# MICHA_nextPCB_servoA2.net
KiCad netlist of a schematic drawn in EAGLE
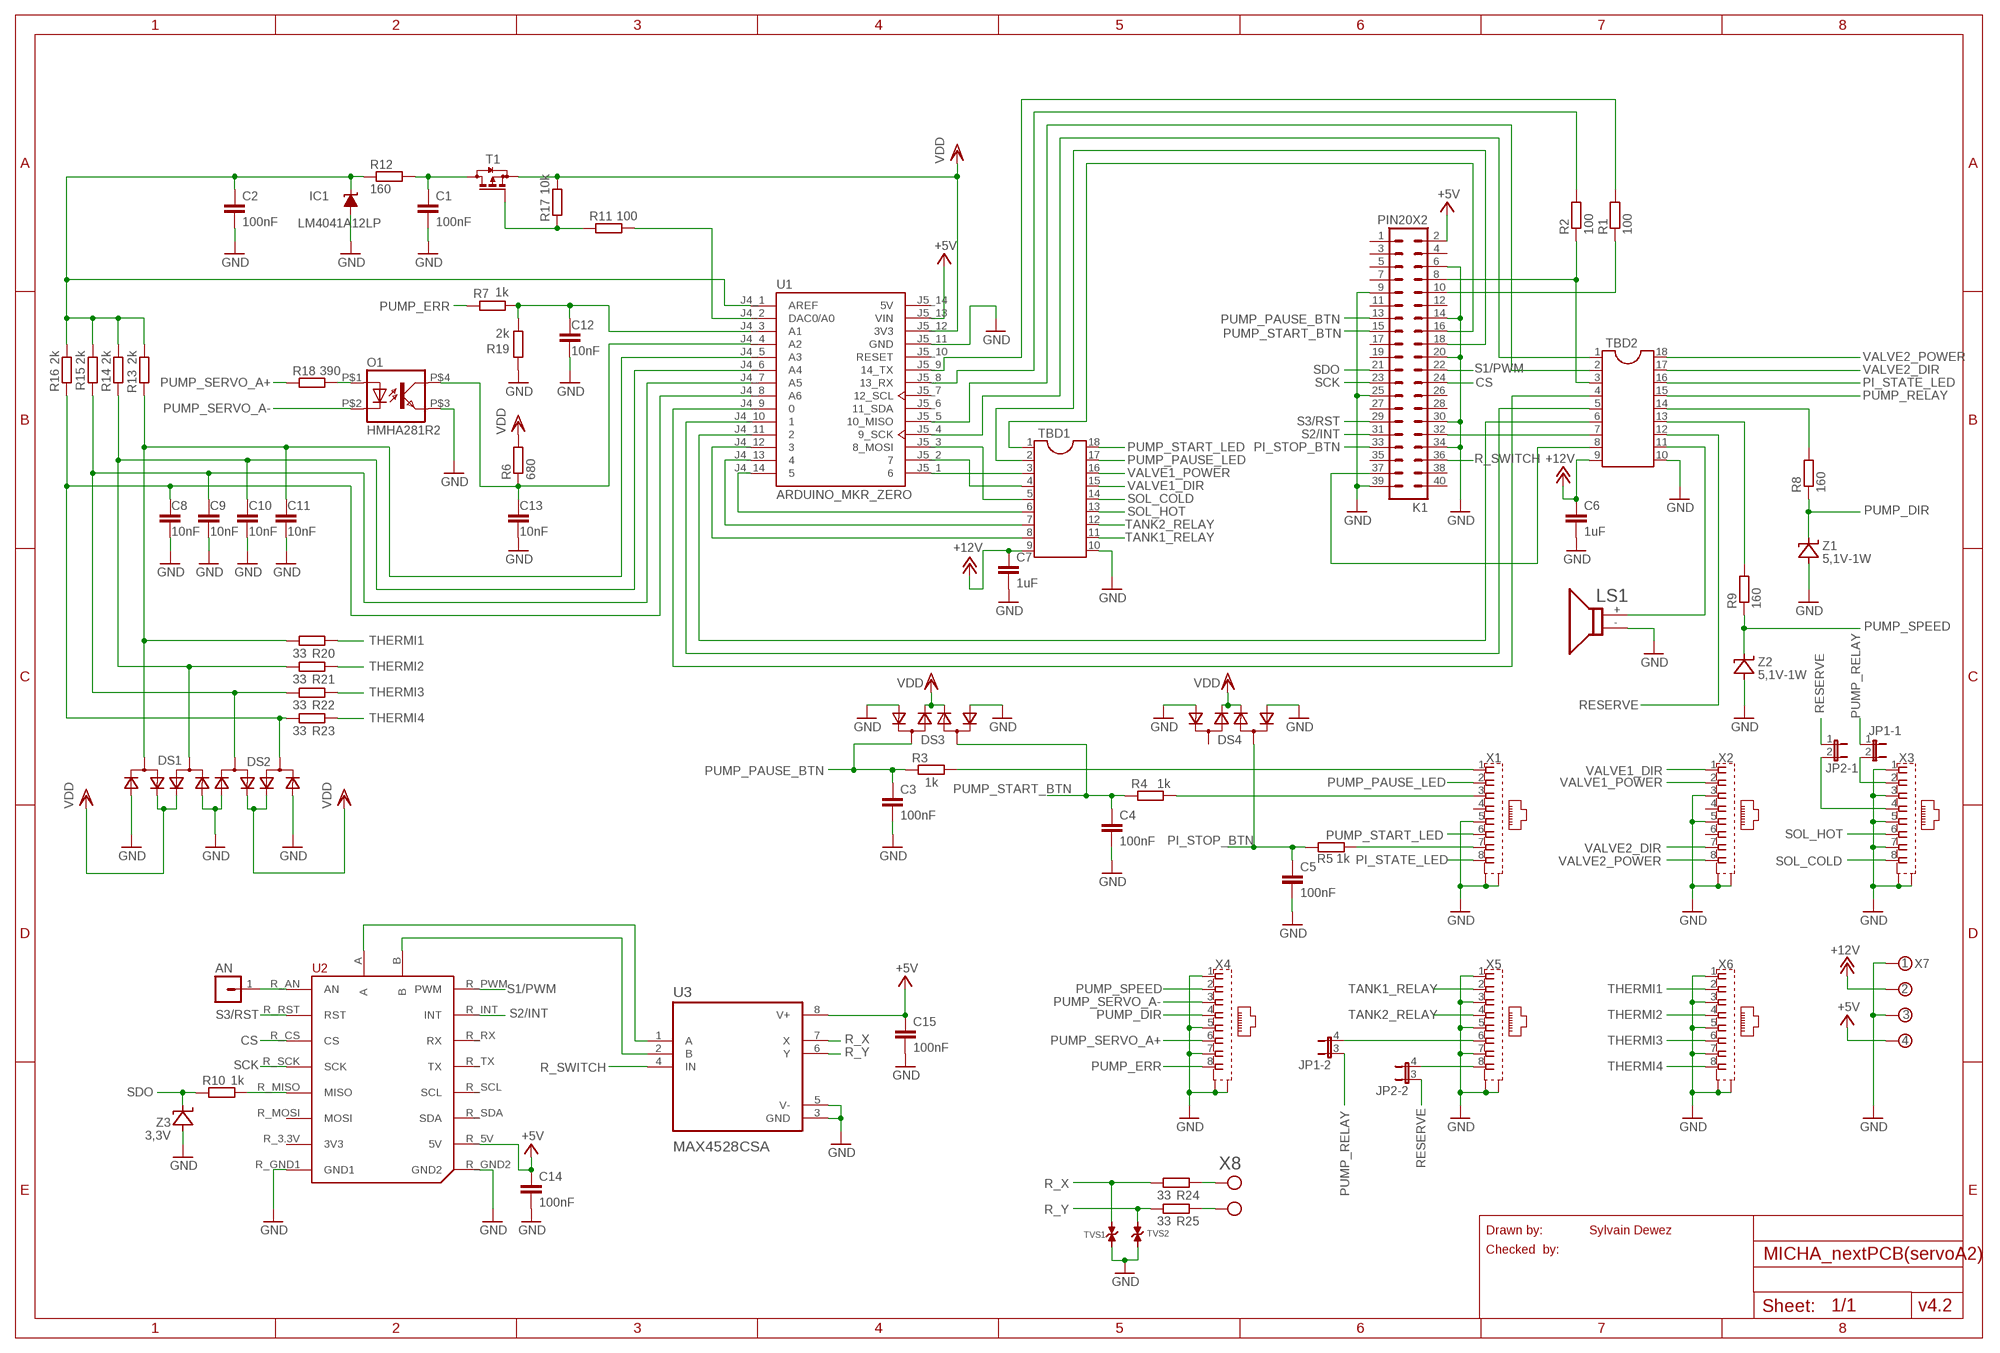
[diagram p0: schematic, sheet 1]

(export (version "E")
  (design (tool "Eeschema 10.0.6"))
  (components
    (comp (ref "AN")
      (value "MA01_PINHEADER")
      (footprint "eagle-import:MA01")
      (libsource (lib "eagle-import") (part "MA01_PINHEADER"))
    )
    (comp (ref "C1")
      (value "100nF")
      (footprint "eagle-import:C1206")
      (libsource (lib "eagle-import") (part "C-EUC1206"))
    )
    (comp (ref "C2")
      (value "100nF")
      (footprint "eagle-import:C1206")
      (libsource (lib "eagle-import") (part "C-EUC1206"))
    )
    (comp (ref "C3")
      (value "100nF")
      (footprint "eagle-import:C1206")
      (libsource (lib "eagle-import") (part "C-EUC1206"))
    )
    (comp (ref "C4")
      (value "100nF")
      (footprint "eagle-import:C1206")
      (libsource (lib "eagle-import") (part "C-EUC1206"))
    )
    (comp (ref "C5")
      (value "100nF")
      (footprint "eagle-import:C1206")
      (libsource (lib "eagle-import") (part "C-EUC1206"))
    )
    (comp (ref "C6")
      (value "1uF")
      (footprint "eagle-import:C1206")
      (libsource (lib "eagle-import") (part "C-EUC1206"))
    )
    (comp (ref "C7")
      (value "1uF")
      (footprint "eagle-import:C1206")
      (libsource (lib "eagle-import") (part "C-EUC1206"))
    )
    (comp (ref "C8")
      (value "10nF")
      (footprint "eagle-import:C1206")
      (libsource (lib "eagle-import") (part "C-EUC1206"))
    )
    (comp (ref "C9")
      (value "10nF")
      (footprint "eagle-import:C1206")
      (libsource (lib "eagle-import") (part "C-EUC1206"))
    )
    (comp (ref "C10")
      (value "10nF")
      (footprint "eagle-import:C1206")
      (libsource (lib "eagle-import") (part "C-EUC1206"))
    )
    (comp (ref "C11")
      (value "10nF")
      (footprint "eagle-import:C1206")
      (libsource (lib "eagle-import") (part "C-EUC1206"))
    )
    (comp (ref "C12")
      (value "10nF")
      (footprint "eagle-import:C1206")
      (libsource (lib "eagle-import") (part "C-EUC1206"))
    )
    (comp (ref "C13")
      (value "10nF")
      (footprint "eagle-import:C1206")
      (libsource (lib "eagle-import") (part "C-EUC1206"))
    )
    (comp (ref "C14")
      (value "100nF")
      (footprint "eagle-import:C1206")
      (libsource (lib "eagle-import") (part "C-EUC1206"))
    )
    (comp (ref "C15")
      (value "100nF")
      (footprint "eagle-import:C1206")
      (libsource (lib "eagle-import") (part "C-EUC1206"))
    )
    (comp (ref "DS1")
      (value "SDM10M45SD")
      (footprint "eagle-import:SDM10M45SD_SOT-26")
      (libsource (lib "eagle-import") (part "SDM10M45SD"))
    )
    (comp (ref "DS2")
      (value "SDM10M45SD")
      (footprint "eagle-import:SDM10M45SD_SOT-26")
      (libsource (lib "eagle-import") (part "SDM10M45SD"))
    )
    (comp (ref "DS3")
      (value "SDM10M45SD")
      (footprint "eagle-import:SDM10M45SD_SOT-26")
      (libsource (lib "eagle-import") (part "SDM10M45SD"))
    )
    (comp (ref "DS4")
      (value "SDM10M45SD")
      (footprint "eagle-import:SDM10M45SD_SOT-26")
      (libsource (lib "eagle-import") (part "SDM10M45SD"))
    )
    (comp (ref "IC1")
      (value "LM4041A12LP")
      (footprint "eagle-import:LP_O-PBCY-W3")
      (libsource (lib "eagle-import") (part "LM4041LPA12"))
    )
    (comp (ref "JP1")
      (value "JP2QE")
      (footprint "eagle-import:JP2Q")
      (libsource (lib "eagle-import") (part "JP2QE"))
    )
    (comp (ref "JP2")
      (value "JP2QE")
      (footprint "eagle-import:JP2Q")
      (libsource (lib "eagle-import") (part "JP2QE"))
    )
    (comp (ref "K1")
      (value "PIN20X2")
      (footprint "eagle-import:PIN_20X2")
      (libsource (lib "eagle-import") (part "PIN20X2"))
    )
    (comp (ref "LS1")
      (value "RSPRO-BUZZER-7800743")
      (footprint "eagle-import:RSPRO-BUZZER-7800743")
      (libsource (lib "eagle-import") (part "RSPRO-BUZZER-7800743"))
    )
    (comp (ref "O1")
      (value "HMHA281R2")
      (footprint "eagle-import:HMHA281R2")
      (libsource (lib "eagle-import") (part "HMHA281R2"))
    )
    (comp (ref "R1")
      (value "100")
      (footprint "eagle-import:R1206")
      (libsource (lib "eagle-import") (part "resistor_R-EU_R1206"))
    )
    (comp (ref "R2")
      (value "100")
      (footprint "eagle-import:R1206")
      (libsource (lib "eagle-import") (part "resistor_R-EU_R1206"))
    )
    (comp (ref "R3")
      (value "1k")
      (footprint "eagle-import:R1206")
      (libsource (lib "eagle-import") (part "resistor_R-EU_R1206"))
    )
    (comp (ref "R4")
      (value "1k")
      (footprint "eagle-import:R1206")
      (libsource (lib "eagle-import") (part "resistor_R-EU_R1206"))
    )
    (comp (ref "R5")
      (value "1k")
      (footprint "eagle-import:R1206")
      (libsource (lib "eagle-import") (part "resistor_R-EU_R1206"))
    )
    (comp (ref "R6")
      (value "680")
      (footprint "eagle-import:R1206")
      (libsource (lib "eagle-import") (part "resistor_R-EU_R1206"))
    )
    (comp (ref "R7")
      (value "1k")
      (footprint "eagle-import:R1206")
      (libsource (lib "eagle-import") (part "resistor_R-EU_R1206"))
    )
    (comp (ref "R8")
      (value "160")
      (footprint "eagle-import:R1206")
      (libsource (lib "eagle-import") (part "R-EU_R1206"))
    )
    (comp (ref "R9")
      (value "160")
      (footprint "eagle-import:R1206")
      (libsource (lib "eagle-import") (part "R-EU_R1206"))
    )
    (comp (ref "R10")
      (value "1k")
      (footprint "eagle-import:R1206")
      (libsource (lib "eagle-import") (part "resistor_R-EU_R1206"))
    )
    (comp (ref "R11")
      (value "100")
      (footprint "eagle-import:R1206")
      (libsource (lib "eagle-import") (part "resistor_R-EU_R1206"))
    )
    (comp (ref "R12")
      (value "160")
      (footprint "eagle-import:R1206")
      (libsource (lib "eagle-import") (part "R-EU_R1206"))
    )
    (comp (ref "R13")
      (value "2k")
      (footprint "eagle-import:R1206")
      (libsource (lib "eagle-import") (part "resistor_R-EU_R1206"))
    )
    (comp (ref "R14")
      (value "2k")
      (footprint "eagle-import:R1206")
      (libsource (lib "eagle-import") (part "resistor_R-EU_R1206"))
    )
    (comp (ref "R15")
      (value "2k")
      (footprint "eagle-import:R1206")
      (libsource (lib "eagle-import") (part "resistor_R-EU_R1206"))
    )
    (comp (ref "R16")
      (value "2k")
      (footprint "eagle-import:R1206")
      (libsource (lib "eagle-import") (part "resistor_R-EU_R1206"))
    )
    (comp (ref "R17")
      (value "10k")
      (footprint "eagle-import:R1206")
      (libsource (lib "eagle-import") (part "resistor_R-EU_R1206"))
    )
    (comp (ref "R18")
      (value "390")
      (footprint "eagle-import:R1206")
      (libsource (lib "eagle-import") (part "resistor_R-EU_R1206"))
    )
    (comp (ref "R19")
      (value "2k")
      (footprint "eagle-import:R1206")
      (libsource (lib "eagle-import") (part "resistor_R-EU_R1206"))
    )
    (comp (ref "R20")
      (value "33")
      (footprint "eagle-import:R1206")
      (libsource (lib "eagle-import") (part "resistor_R-EU_R1206"))
    )
    (comp (ref "R21")
      (value "33")
      (footprint "eagle-import:R1206")
      (libsource (lib "eagle-import") (part "resistor_R-EU_R1206"))
    )
    (comp (ref "R22")
      (value "33")
      (footprint "eagle-import:R1206")
      (libsource (lib "eagle-import") (part "resistor_R-EU_R1206"))
    )
    (comp (ref "R23")
      (value "33")
      (footprint "eagle-import:R1206")
      (libsource (lib "eagle-import") (part "resistor_R-EU_R1206"))
    )
    (comp (ref "R24")
      (value "33")
      (footprint "eagle-import:R1206")
      (libsource (lib "eagle-import") (part "resistor_R-EU_R1206"))
    )
    (comp (ref "R25")
      (value "33")
      (footprint "eagle-import:R1206")
      (libsource (lib "eagle-import") (part "resistor_R-EU_R1206"))
    )
    (comp (ref "T1")
      (value "BSS84")
      (footprint "eagle-import:SOT23")
      (libsource (lib "eagle-import") (part "BSS84"))
    )
    (comp (ref "TBD1")
      (value "DIL18S")
      (footprint "eagle-import:SOCKET-18")
      (libsource (lib "eagle-import") (part "DIL18S"))
    )
    (comp (ref "TBD2")
      (value "DIL18S")
      (footprint "eagle-import:SOCKET-18")
      (libsource (lib "eagle-import") (part "DIL18S"))
    )
    (comp (ref "TVS1")
      (value "TVS_SOD123")
      (footprint "eagle-import:TVS_SOD123")
      (libsource (lib "eagle-import") (part "TVS_SOD123"))
    )
    (comp (ref "TVS2")
      (value "TVS_SOD123")
      (footprint "eagle-import:TVS_SOD123")
      (libsource (lib "eagle-import") (part "TVS_SOD123"))
    )
    (comp (ref "U1")
      (value "ARDUINO_MKR_ZERO")
      (footprint "eagle-import:MODULE_ARDUINO_MKR_ZERO")
      (fields (field (name "MF") "Arduino") (field (name "MP") "ARDUINO MKR ZERO"))
      (libsource (lib "eagle-import") (part "ARDUINO_MKR_ZERO"))
    )
    (comp (ref "U2")
      (value "MIKROE_CLICK_UPGRADE")
      (footprint "eagle-import:MIKROE_BUS_MIDI_UPGRADE")
      (libsource (lib "eagle-import") (part "MIKROE_CLICK_UPGRADE"))
    )
    (comp (ref "U3")
      (value "MAX4528CSA")
      (footprint "eagle-import:SOIC127P600X175-8N")
      (fields (field (name "MF") "Maxim Integrated") (field (name "MP") "MAX4528CSA+"))
      (libsource (lib "eagle-import") (part "MAX4528CSA"))
    )
    (comp (ref "X1")
      (value "SS-7188S-A-NF_V2")
      (footprint "eagle-import:BEL_SS-7188S-A-NF")
      (fields (field (name "MF") "Stewart Connector") (field (name "MP") "SS-7188S-A-NF"))
      (libsource (lib "eagle-import") (part "SS-7188S-A-NF_V2"))
    )
    (comp (ref "X2")
      (value "SS-7188S-A-NF_V2")
      (footprint "eagle-import:BEL_SS-7188S-A-NF")
      (fields (field (name "MF") "Stewart Connector") (field (name "MP") "SS-7188S-A-NF"))
      (libsource (lib "eagle-import") (part "SS-7188S-A-NF_V2"))
    )
    (comp (ref "X3")
      (value "SS-7188S-A-NF_V2")
      (footprint "eagle-import:BEL_SS-7188S-A-NF")
      (fields (field (name "MF") "Stewart Connector") (field (name "MP") "SS-7188S-A-NF"))
      (libsource (lib "eagle-import") (part "SS-7188S-A-NF_V2"))
    )
    (comp (ref "X4")
      (value "SS-7188S-A-NF_V2")
      (footprint "eagle-import:BEL_SS-7188S-A-NF")
      (fields (field (name "MF") "Stewart Connector") (field (name "MP") "SS-7188S-A-NF"))
      (libsource (lib "eagle-import") (part "SS-7188S-A-NF_V2"))
    )
    (comp (ref "X5")
      (value "SS-7188S-A-NF_V2")
      (footprint "eagle-import:BEL_SS-7188S-A-NF")
      (fields (field (name "MF") "Stewart Connector") (field (name "MP") "SS-7188S-A-NF"))
      (libsource (lib "eagle-import") (part "SS-7188S-A-NF_V2"))
    )
    (comp (ref "X6")
      (value "SS-7188S-A-NF_V2")
      (footprint "eagle-import:BEL_SS-7188S-A-NF")
      (fields (field (name "MF") "Stewart Connector") (field (name "MP") "SS-7188S-A-NF"))
      (libsource (lib "eagle-import") (part "SS-7188S-A-NF_V2"))
    )
    (comp (ref "X7")
      (value "BUCHANAN_4_3.5MM")
      (footprint "eagle-import:BUCHANAN_4_3.5MM")
      (libsource (lib "eagle-import") (part "BUCHANAN_4_3.5MM"))
    )
    (comp (ref "X8")
      (value "MPT_0,5/_2-2,54_1725656_2")
      (footprint "eagle-import:PH_MPT_0,5__2-2,54_1725656")
      (fields (field (name "MF") "Phoenix Contact") (field (name "MP") "MPT 0,5/ 2-2,54 1725656"))
      (libsource (lib "eagle-import") (part "MPT_0,5/_2-2,54_1725656_2"))
    )
    (comp (ref "Z1")
      (value "5,1V-1W")
      (footprint "eagle-import:ZENER_SMA")
      (libsource (lib "eagle-import") (part "ZENER_SMA"))
    )
    (comp (ref "Z2")
      (value "5,1V-1W")
      (footprint "eagle-import:ZENER_SMA")
      (libsource (lib "eagle-import") (part "ZENER_SMA"))
    )
    (comp (ref "Z3")
      (value "3,3V")
      (footprint "eagle-import:ZENER_SMA")
      (libsource (lib "eagle-import") (part "ZENER_SMA"))
    )
  )
  (nets
    (net (code "1") (name "+5V") (class "Default")
      (node (ref "C14") (pin "1") (pinfunction "1_1") (pintype "passive"))
      (node (ref "C15") (pin "1") (pinfunction "1_1") (pintype "passive"))
      (node (ref "K1") (pin "2") (pinfunction "2_2") (pintype "passive"))
      (node (ref "U1") (pin "J5_13") (pinfunction "VIN_J5_13") (pintype "power_in"))
      (node (ref "U2") (pin "R_5V") (pinfunction "5V_R_5V") (pintype "bidirectional"))
      (node (ref "U3") (pin "8") (pinfunction "V+_8") (pintype "power_in"))
      (node (ref "X7") (pin "4") (pinfunction "KL3_4") (pintype "passive"))
    )
    (net (code "2") (name "+12V") (class "Default")
      (node (ref "C6") (pin "1") (pinfunction "1_1") (pintype "passive"))
      (node (ref "C7") (pin "1") (pinfunction "1_1") (pintype "passive"))
      (node (ref "TBD1") (pin "9") (pinfunction "9_9") (pintype "passive"))
      (node (ref "TBD2") (pin "9") (pinfunction "9_9") (pintype "passive"))
      (node (ref "X7") (pin "2") (pinfunction "KL1_2") (pintype "passive"))
    )
    (net (code "3") (name "/5V") (class "Default")
      (node (ref "U1") (pin "J5_14") (pinfunction "5V_J5_14") (pintype "power_in"))
    )
    (net (code "4") (name "/CS") (class "Default")
      (node (ref "K1") (pin "24") (pinfunction "24_24") (pintype "passive"))
      (node (ref "U2") (pin "R_CS") (pinfunction "CS_R_CS") (pintype "bidirectional"))
    )
    (net (code "5") (name "/PI_STATE_LED") (class "Default")
      (node (ref "TBD2") (pin "16") (pinfunction "16_16") (pintype "passive"))
      (node (ref "X1") (pin "8") (pinfunction "8_8") (pintype "passive"))
    )
    (net (code "6") (name "/PI_STOP_BTN") (class "Default")
      (node (ref "C5") (pin "1") (pinfunction "1_1") (pintype "passive"))
      (node (ref "DS4") (pin "3") (pinfunction "C1_3") (pintype "passive"))
      (node (ref "K1") (pin "33") (pinfunction "33_33") (pintype "passive"))
      (node (ref "R5") (pin "1") (pinfunction "1_1") (pintype "passive"))
    )
    (net (code "7") (name "/PUMP_DIR") (class "Default")
      (node (ref "R8") (pin "1") (pinfunction "1_1") (pintype "passive"))
      (node (ref "X4") (pin "4") (pinfunction "4_4") (pintype "passive"))
      (node (ref "Z1") (pin "C") (pinfunction "C_C") (pintype "passive"))
    )
    (net (code "8") (name "/PUMP_ERR") (class "Default")
      (node (ref "R7") (pin "1") (pinfunction "1_1") (pintype "passive"))
      (node (ref "X4") (pin "8") (pinfunction "8_8") (pintype "passive"))
    )
    (net (code "9") (name "/PUMP_PAUSE_BTN") (class "Default")
      (node (ref "C3") (pin "1") (pinfunction "1_1") (pintype "passive"))
      (node (ref "DS3") (pin "6") (pinfunction "C_6") (pintype "passive"))
      (node (ref "K1") (pin "13") (pinfunction "13_13") (pintype "passive"))
      (node (ref "R3") (pin "1") (pinfunction "1_1") (pintype "passive"))
    )
    (net (code "10") (name "/PUMP_PAUSE_LED") (class "Default")
      (node (ref "TBD1") (pin "17") (pinfunction "17_17") (pintype "passive"))
      (node (ref "X1") (pin "2") (pinfunction "2_2") (pintype "passive"))
    )
    (net (code "11") (name "/PUMP_RELAY") (class "Default")
      (node (ref "JP1") (pin "1") (pinfunction "1_1") (pintype "passive"))
      (node (ref "JP1") (pin "3") (pinfunction "1_3") (pintype "passive"))
      (node (ref "TBD2") (pin "15") (pinfunction "15_15") (pintype "passive"))
    )
    (net (code "12") (name "/PUMP_SERVO_A+") (class "Default")
      (node (ref "R18") (pin "1") (pinfunction "1_1") (pintype "passive"))
      (node (ref "X4") (pin "6") (pinfunction "6_6") (pintype "passive"))
    )
    (net (code "13") (name "/PUMP_SERVO_A-") (class "Default")
      (node (ref "O1") (pin "P$2") (pinfunction "C_P$2") (pintype "passive"))
      (node (ref "X4") (pin "3") (pinfunction "3_3") (pintype "passive"))
    )
    (net (code "14") (name "/PUMP_SPEED") (class "Default")
      (node (ref "R9") (pin "1") (pinfunction "1_1") (pintype "passive"))
      (node (ref "X4") (pin "2") (pinfunction "2_2") (pintype "passive"))
      (node (ref "Z2") (pin "C") (pinfunction "C_C") (pintype "passive"))
    )
    (net (code "15") (name "/PUMP_START_BTN") (class "Default")
      (node (ref "C4") (pin "1") (pinfunction "1_1") (pintype "passive"))
      (node (ref "DS3") (pin "3") (pinfunction "C1_3") (pintype "passive"))
      (node (ref "K1") (pin "15") (pinfunction "15_15") (pintype "passive"))
      (node (ref "R4") (pin "1") (pinfunction "1_1") (pintype "passive"))
    )
    (net (code "16") (name "/PUMP_START_LED") (class "Default")
      (node (ref "TBD1") (pin "18") (pinfunction "18_18") (pintype "passive"))
      (node (ref "X1") (pin "6") (pinfunction "6_6") (pintype "passive"))
    )
    (net (code "17") (name "/RESERVE") (class "Default")
      (node (ref "JP2") (pin "1") (pinfunction "1_1") (pintype "passive"))
      (node (ref "JP2") (pin "3") (pinfunction "1_3") (pintype "passive"))
      (node (ref "TBD2") (pin "12") (pinfunction "12_12") (pintype "passive"))
    )
    (net (code "18") (name "/R_SWITCH") (class "Default")
      (node (ref "K1") (pin "36") (pinfunction "36_36") (pintype "passive"))
      (node (ref "U3") (pin "4") (pinfunction "IN_4") (pintype "input"))
    )
    (net (code "19") (name "/R_X") (class "Default")
      (node (ref "R24") (pin "1") (pinfunction "1_1") (pintype "passive"))
      (node (ref "TVS1") (pin "P$1") (pinfunction "C_P$1") (pintype "passive"))
      (node (ref "U3") (pin "7") (pinfunction "X_7") (pintype "output"))
    )
    (net (code "20") (name "/R_Y") (class "Default")
      (node (ref "R25") (pin "1") (pinfunction "1_1") (pintype "passive"))
      (node (ref "TVS2") (pin "P$1") (pinfunction "C_P$1") (pintype "passive"))
      (node (ref "U3") (pin "6") (pinfunction "Y_6") (pintype "output"))
    )
    (net (code "21") (name "/S1{slash}PWM") (class "Default")
      (node (ref "K1") (pin "22") (pinfunction "22_22") (pintype "passive"))
      (node (ref "U2") (pin "R_PWM") (pinfunction "PWM_R_PWM") (pintype "bidirectional"))
    )
    (net (code "22") (name "/S2{slash}INT") (class "Default")
      (node (ref "K1") (pin "31") (pinfunction "31_31") (pintype "passive"))
      (node (ref "U2") (pin "R_INT") (pinfunction "INT_R_INT") (pintype "bidirectional"))
    )
    (net (code "23") (name "/S3{slash}RST") (class "Default")
      (node (ref "K1") (pin "29") (pinfunction "29_29") (pintype "passive"))
      (node (ref "U2") (pin "R_RST") (pinfunction "RST_R_RST") (pintype "bidirectional"))
    )
    (net (code "24") (name "/SCK") (class "Default")
      (node (ref "K1") (pin "23") (pinfunction "23_23") (pintype "passive"))
      (node (ref "U2") (pin "R_SCK") (pinfunction "SCK_R_SCK") (pintype "bidirectional"))
    )
    (net (code "25") (name "/SDO") (class "Default")
      (node (ref "K1") (pin "21") (pinfunction "21_21") (pintype "passive"))
      (node (ref "R10") (pin "1") (pinfunction "1_1") (pintype "passive"))
      (node (ref "Z3") (pin "C") (pinfunction "C_C") (pintype "passive"))
    )
    (net (code "26") (name "/SOL_COLD") (class "Default")
      (node (ref "TBD1") (pin "14") (pinfunction "14_14") (pintype "passive"))
      (node (ref "X3") (pin "8") (pinfunction "8_8") (pintype "passive"))
    )
    (net (code "27") (name "/SOL_HOT") (class "Default")
      (node (ref "TBD1") (pin "13") (pinfunction "13_13") (pintype "passive"))
      (node (ref "X3") (pin "6") (pinfunction "6_6") (pintype "passive"))
    )
    (net (code "28") (name "/TANK1_RELAY") (class "Default")
      (node (ref "TBD1") (pin "11") (pinfunction "11_11") (pintype "passive"))
      (node (ref "X5") (pin "2") (pinfunction "2_2") (pintype "passive"))
    )
    (net (code "29") (name "/TANK2_RELAY") (class "Default")
      (node (ref "TBD1") (pin "12") (pinfunction "12_12") (pintype "passive"))
      (node (ref "X5") (pin "4") (pinfunction "4_4") (pintype "passive"))
    )
    (net (code "30") (name "/THERMI1") (class "Default")
      (node (ref "R20") (pin "2") (pinfunction "2_2") (pintype "passive"))
      (node (ref "X6") (pin "2") (pinfunction "2_2") (pintype "passive"))
    )
    (net (code "31") (name "/THERMI2") (class "Default")
      (node (ref "R21") (pin "2") (pinfunction "2_2") (pintype "passive"))
      (node (ref "X6") (pin "4") (pinfunction "4_4") (pintype "passive"))
    )
    (net (code "32") (name "/THERMI3") (class "Default")
      (node (ref "R22") (pin "2") (pinfunction "2_2") (pintype "passive"))
      (node (ref "X6") (pin "6") (pinfunction "6_6") (pintype "passive"))
    )
    (net (code "33") (name "/THERMI4") (class "Default")
      (node (ref "R23") (pin "2") (pinfunction "2_2") (pintype "passive"))
      (node (ref "X6") (pin "8") (pinfunction "8_8") (pintype "passive"))
    )
    (net (code "34") (name "/VALVE1_DIR") (class "Default")
      (node (ref "TBD1") (pin "15") (pinfunction "15_15") (pintype "passive"))
      (node (ref "X2") (pin "1") (pinfunction "1_1") (pintype "passive"))
    )
    (net (code "35") (name "/VALVE1_POWER") (class "Default")
      (node (ref "TBD1") (pin "16") (pinfunction "16_16") (pintype "passive"))
      (node (ref "X2") (pin "2") (pinfunction "2_2") (pintype "passive"))
    )
    (net (code "36") (name "/VALVE2_DIR") (class "Default")
      (node (ref "TBD2") (pin "17") (pinfunction "17_17") (pintype "passive"))
      (node (ref "X2") (pin "7") (pinfunction "7_7") (pintype "passive"))
    )
    (net (code "37") (name "/VALVE2_POWER") (class "Default")
      (node (ref "TBD2") (pin "18") (pinfunction "18_18") (pintype "passive"))
      (node (ref "X2") (pin "8") (pinfunction "8_8") (pintype "passive"))
    )
    (net (code "38") (name "GND") (class "Default")
      (node (ref "C1") (pin "2") (pinfunction "2_2") (pintype "passive"))
      (node (ref "C10") (pin "2") (pinfunction "2_2") (pintype "passive"))
      (node (ref "C11") (pin "2") (pinfunction "2_2") (pintype "passive"))
      (node (ref "C12") (pin "2") (pinfunction "2_2") (pintype "passive"))
      (node (ref "C13") (pin "2") (pinfunction "2_2") (pintype "passive"))
      (node (ref "C14") (pin "2") (pinfunction "2_2") (pintype "passive"))
      (node (ref "C15") (pin "2") (pinfunction "2_2") (pintype "passive"))
      (node (ref "C2") (pin "2") (pinfunction "2_2") (pintype "passive"))
      (node (ref "C3") (pin "2") (pinfunction "2_2") (pintype "passive"))
      (node (ref "C4") (pin "2") (pinfunction "2_2") (pintype "passive"))
      (node (ref "C5") (pin "2") (pinfunction "2_2") (pintype "passive"))
      (node (ref "C6") (pin "2") (pinfunction "2_2") (pintype "passive"))
      (node (ref "C7") (pin "2") (pinfunction "2_2") (pintype "passive"))
      (node (ref "C8") (pin "2") (pinfunction "2_2") (pintype "passive"))
      (node (ref "C9") (pin "2") (pinfunction "2_2") (pintype "passive"))
      (node (ref "DS1") (pin "1") (pinfunction "A2_1") (pintype "passive"))
      (node (ref "DS1") (pin "4") (pinfunction "A3_4") (pintype "passive"))
      (node (ref "DS2") (pin "1") (pinfunction "A2_1") (pintype "passive"))
      (node (ref "DS2") (pin "4") (pinfunction "A3_4") (pintype "passive"))
      (node (ref "DS3") (pin "1") (pinfunction "A2_1") (pintype "passive"))
      (node (ref "DS3") (pin "4") (pinfunction "A3_4") (pintype "passive"))
      (node (ref "DS4") (pin "1") (pinfunction "A2_1") (pintype "passive"))
      (node (ref "DS4") (pin "4") (pinfunction "A3_4") (pintype "passive"))
      (node (ref "IC1") (pin "3") (pinfunction "A_3") (pintype "passive"))
      (node (ref "K1") (pin "14") (pinfunction "14_14") (pintype "passive"))
      (node (ref "K1") (pin "20") (pinfunction "20_20") (pintype "passive"))
      (node (ref "K1") (pin "25") (pinfunction "25_25") (pintype "passive"))
      (node (ref "K1") (pin "30") (pinfunction "30_30") (pintype "passive"))
      (node (ref "K1") (pin "34") (pinfunction "34_34") (pintype "passive"))
      (node (ref "K1") (pin "39") (pinfunction "39_39") (pintype "passive"))
      (node (ref "K1") (pin "6") (pinfunction "6_6") (pintype "passive"))
      (node (ref "K1") (pin "9") (pinfunction "9_9") (pintype "passive"))
      (node (ref "LS1") (pin "-") (pinfunction "2_-") (pintype "passive"))
      (node (ref "O1") (pin "P$3") (pinfunction "EMIT_P$3") (pintype "passive"))
      (node (ref "R19") (pin "1") (pinfunction "1_1") (pintype "passive"))
      (node (ref "TBD1") (pin "10") (pinfunction "10_10") (pintype "passive"))
      (node (ref "TBD2") (pin "10") (pinfunction "10_10") (pintype "passive"))
      (node (ref "TVS1") (pin "P$2") (pinfunction "C1_P$2") (pintype "passive"))
      (node (ref "TVS2") (pin "P$2") (pinfunction "C1_P$2") (pintype "passive"))
      (node (ref "U1") (pin "J5_11") (pinfunction "GND_J5_11") (pintype "power_in"))
      (node (ref "U2") (pin "R_GND1") (pinfunction "GND1_R_GND1") (pintype "bidirectional"))
      (node (ref "U2") (pin "R_GND2") (pinfunction "GND2_R_GND2") (pintype "bidirectional"))
      (node (ref "U3") (pin "3") (pinfunction "GND_3") (pintype "power_in"))
      (node (ref "U3") (pin "5") (pinfunction "V-_5") (pintype "power_in"))
      (node (ref "X1") (pin "5") (pinfunction "5_5") (pintype "passive"))
      (node (ref "X1") (pin "S1") (pinfunction "GND1_S1") (pintype "passive"))
      (node (ref "X1") (pin "S2") (pinfunction "GND2_S2") (pintype "passive"))
      (node (ref "X2") (pin "3") (pinfunction "3_3") (pintype "passive"))
      (node (ref "X2") (pin "5") (pinfunction "5_5") (pintype "passive"))
      (node (ref "X2") (pin "S1") (pinfunction "GND1_S1") (pintype "passive"))
      (node (ref "X2") (pin "S2") (pinfunction "GND2_S2") (pintype "passive"))
      (node (ref "X3") (pin "1") (pinfunction "1_1") (pintype "passive"))
      (node (ref "X3") (pin "3") (pinfunction "3_3") (pintype "passive"))
      (node (ref "X3") (pin "5") (pinfunction "5_5") (pintype "passive"))
      (node (ref "X3") (pin "7") (pinfunction "7_7") (pintype "passive"))
      (node (ref "X3") (pin "S1") (pinfunction "GND1_S1") (pintype "passive"))
      (node (ref "X3") (pin "S2") (pinfunction "GND2_S2") (pintype "passive"))
      (node (ref "X4") (pin "1") (pinfunction "1_1") (pintype "passive"))
      (node (ref "X4") (pin "5") (pinfunction "5_5") (pintype "passive"))
      (node (ref "X4") (pin "7") (pinfunction "7_7") (pintype "passive"))
      (node (ref "X4") (pin "S1") (pinfunction "GND1_S1") (pintype "passive"))
      (node (ref "X4") (pin "S2") (pinfunction "GND2_S2") (pintype "passive"))
      (node (ref "X5") (pin "1") (pinfunction "1_1") (pintype "passive"))
      (node (ref "X5") (pin "3") (pinfunction "3_3") (pintype "passive"))
      (node (ref "X5") (pin "5") (pinfunction "5_5") (pintype "passive"))
      (node (ref "X5") (pin "7") (pinfunction "7_7") (pintype "passive"))
      (node (ref "X5") (pin "S1") (pinfunction "GND1_S1") (pintype "passive"))
      (node (ref "X5") (pin "S2") (pinfunction "GND2_S2") (pintype "passive"))
      (node (ref "X6") (pin "1") (pinfunction "1_1") (pintype "passive"))
      (node (ref "X6") (pin "3") (pinfunction "3_3") (pintype "passive"))
      (node (ref "X6") (pin "5") (pinfunction "5_5") (pintype "passive"))
      (node (ref "X6") (pin "7") (pinfunction "7_7") (pintype "passive"))
      (node (ref "X6") (pin "S1") (pinfunction "GND1_S1") (pintype "passive"))
      (node (ref "X6") (pin "S2") (pinfunction "GND2_S2") (pintype "passive"))
      (node (ref "X7") (pin "1") (pinfunction "KL_1") (pintype "passive"))
      (node (ref "X7") (pin "3") (pinfunction "KL2_3") (pintype "passive"))
      (node (ref "Z1") (pin "A") (pinfunction "A_A") (pintype "passive"))
      (node (ref "Z2") (pin "A") (pinfunction "A_A") (pintype "passive"))
      (node (ref "Z3") (pin "A") (pinfunction "A_A") (pintype "passive"))
    )
    (net (code "39") (name "Net-(DS1-C)") (class "Default")
      (node (ref "C10") (pin "1") (pinfunction "1_1") (pintype "passive"))
      (node (ref "DS1") (pin "6") (pinfunction "C_6") (pintype "passive"))
      (node (ref "R14") (pin "2") (pinfunction "2_2") (pintype "passive"))
      (node (ref "R21") (pin "1") (pinfunction "1_1") (pintype "passive"))
      (node (ref "U1") (pin "J4_6") (pinfunction "A4_J4_6") (pintype "bidirectional"))
    )
    (net (code "40") (name "Net-(DS1-C1)") (class "Default")
      (node (ref "C11") (pin "1") (pinfunction "1_1") (pintype "passive"))
      (node (ref "DS1") (pin "3") (pinfunction "C1_3") (pintype "passive"))
      (node (ref "R13") (pin "2") (pinfunction "2_2") (pintype "passive"))
      (node (ref "R20") (pin "1") (pinfunction "1_1") (pintype "passive"))
      (node (ref "U1") (pin "J4_5") (pinfunction "A3_J4_5") (pintype "bidirectional"))
    )
    (net (code "41") (name "Net-(DS2-C)") (class "Default")
      (node (ref "C8") (pin "1") (pinfunction "1_1") (pintype "passive"))
      (node (ref "DS2") (pin "6") (pinfunction "C_6") (pintype "passive"))
      (node (ref "R16") (pin "2") (pinfunction "2_2") (pintype "passive"))
      (node (ref "R23") (pin "1") (pinfunction "1_1") (pintype "passive"))
      (node (ref "U1") (pin "J4_8") (pinfunction "A6_J4_8") (pintype "bidirectional"))
    )
    (net (code "42") (name "Net-(DS2-C1)") (class "Default")
      (node (ref "C9") (pin "1") (pinfunction "1_1") (pintype "passive"))
      (node (ref "DS2") (pin "3") (pinfunction "C1_3") (pintype "passive"))
      (node (ref "R15") (pin "2") (pinfunction "2_2") (pintype "passive"))
      (node (ref "R22") (pin "1") (pinfunction "1_1") (pintype "passive"))
      (node (ref "U1") (pin "J4_7") (pinfunction "A5_J4_7") (pintype "bidirectional"))
    )
    (net (code "43") (name "Net-(IC1-C)") (class "Default")
      (node (ref "C2") (pin "1") (pinfunction "1_1") (pintype "passive"))
      (node (ref "IC1") (pin "2") (pinfunction "C_2") (pintype "passive"))
      (node (ref "R12") (pin "1") (pinfunction "1_1") (pintype "passive"))
      (node (ref "R13") (pin "1") (pinfunction "1_1") (pintype "passive"))
      (node (ref "R14") (pin "1") (pinfunction "1_1") (pintype "passive"))
      (node (ref "R15") (pin "1") (pinfunction "1_1") (pintype "passive"))
      (node (ref "R16") (pin "1") (pinfunction "1_1") (pintype "passive"))
      (node (ref "U1") (pin "J4_1") (pinfunction "AREF_J4_1") (pintype "bidirectional"))
    )
    (net (code "44") (name "Net-(JP1-Pad2)") (class "Default")
      (node (ref "JP1") (pin "2") (pinfunction "2_2") (pintype "passive"))
      (node (ref "X3") (pin "2") (pinfunction "2_2") (pintype "passive"))
    )
    (net (code "45") (name "Net-(JP1B-2)") (class "Default")
      (node (ref "JP1") (pin "4") (pinfunction "2_4") (pintype "passive"))
      (node (ref "X5") (pin "6") (pinfunction "6_6") (pintype "passive"))
    )
    (net (code "46") (name "Net-(JP2-Pad2)") (class "Default")
      (node (ref "JP2") (pin "2") (pinfunction "2_2") (pintype "passive"))
      (node (ref "X3") (pin "4") (pinfunction "4_4") (pintype "passive"))
    )
    (net (code "47") (name "Net-(JP2B-2)") (class "Default")
      (node (ref "JP2") (pin "4") (pinfunction "2_4") (pintype "passive"))
      (node (ref "X5") (pin "8") (pinfunction "8_8") (pintype "passive"))
    )
    (net (code "48") (name "Net-(K1-Pad8)") (class "Default")
      (node (ref "K1") (pin "8") (pinfunction "8_8") (pintype "passive"))
      (node (ref "R2") (pin "1") (pinfunction "1_1") (pintype "passive"))
      (node (ref "TBD2") (pin "3") (pinfunction "3_3") (pintype "passive"))
    )
    (net (code "49") (name "Net-(K1-Pad10)") (class "Default")
      (node (ref "K1") (pin "10") (pinfunction "10_10") (pintype "passive"))
      (node (ref "R1") (pin "1") (pinfunction "1_1") (pintype "passive"))
    )
    (net (code "50") (name "Net-(K1-Pad16)") (class "Default")
      (node (ref "K1") (pin "16") (pinfunction "16_16") (pintype "passive"))
      (node (ref "TBD1") (pin "1") (pinfunction "1_1") (pintype "passive"))
    )
    (net (code "51") (name "Net-(K1-Pad18)") (class "Default")
      (node (ref "K1") (pin "18") (pinfunction "18_18") (pintype "passive"))
      (node (ref "TBD1") (pin "2") (pinfunction "2_2") (pintype "passive"))
    )
    (net (code "52") (name "Net-(K1-Pad32)") (class "Default")
      (node (ref "K1") (pin "32") (pinfunction "32_32") (pintype "passive"))
      (node (ref "TBD2") (pin "7") (pinfunction "7_7") (pintype "passive"))
    )
    (net (code "53") (name "Net-(K1-Pad37)") (class "Default")
      (node (ref "K1") (pin "37") (pinfunction "37_37") (pintype "passive"))
      (node (ref "TBD2") (pin "8") (pinfunction "8_8") (pintype "passive"))
    )
    (net (code "54") (name "Net-(LS1-1)") (class "Default")
      (node (ref "LS1") (pin "+") (pinfunction "1_+") (pintype "passive"))
      (node (ref "TBD2") (pin "11") (pinfunction "11_11") (pintype "passive"))
    )
    (net (code "55") (name "Net-(O1-A)") (class "Default")
      (node (ref "O1") (pin "P$1") (pinfunction "A_P$1") (pintype "passive"))
      (node (ref "R18") (pin "2") (pinfunction "2_2") (pintype "passive"))
    )
    (net (code "56") (name "Net-(O1-COL)") (class "Default")
      (node (ref "C13") (pin "1") (pinfunction "1_1") (pintype "passive"))
      (node (ref "O1") (pin "P$4") (pinfunction "COL_P$4") (pintype "passive"))
      (node (ref "R6") (pin "1") (pinfunction "1_1") (pintype "passive"))
      (node (ref "U1") (pin "J4_4") (pinfunction "A2_J4_4") (pintype "bidirectional"))
    )
    (net (code "57") (name "Net-(R3-Pad2)") (class "Default")
      (node (ref "R3") (pin "2") (pinfunction "2_2") (pintype "passive"))
      (node (ref "X1") (pin "1") (pinfunction "1_1") (pintype "passive"))
    )
    (net (code "58") (name "Net-(R4-Pad2)") (class "Default")
      (node (ref "R4") (pin "2") (pinfunction "2_2") (pintype "passive"))
      (node (ref "X1") (pin "3") (pinfunction "3_3") (pintype "passive"))
    )
    (net (code "59") (name "Net-(R5-Pad2)") (class "Default")
      (node (ref "R5") (pin "2") (pinfunction "2_2") (pintype "passive"))
      (node (ref "X1") (pin "7") (pinfunction "7_7") (pintype "passive"))
    )
    (net (code "60") (name "Net-(R8-Pad2)") (class "Default")
      (node (ref "R8") (pin "2") (pinfunction "2_2") (pintype "passive"))
      (node (ref "TBD2") (pin "14") (pinfunction "14_14") (pintype "passive"))
    )
    (net (code "61") (name "Net-(R9-Pad2)") (class "Default")
      (node (ref "R9") (pin "2") (pinfunction "2_2") (pintype "passive"))
      (node (ref "TBD2") (pin "13") (pinfunction "13_13") (pintype "passive"))
    )
    (net (code "62") (name "Net-(T1-D)") (class "Default")
      (node (ref "C1") (pin "1") (pinfunction "1_1") (pintype "passive"))
      (node (ref "R12") (pin "2") (pinfunction "2_2") (pintype "passive"))
      (node (ref "T1") (pin "3") (pinfunction "D_3") (pintype "passive"))
    )
    (net (code "63") (name "Net-(T1-G)") (class "Default")
      (node (ref "R11") (pin "1") (pinfunction "1_1") (pintype "passive"))
      (node (ref "R17") (pin "1") (pinfunction "1_1") (pintype "passive"))
      (node (ref "T1") (pin "1") (pinfunction "G_1") (pintype "passive"))
    )
    (net (code "64") (name "Net-(U1-0)") (class "Default")
      (node (ref "TBD2") (pin "4") (pinfunction "4_4") (pintype "passive"))
      (node (ref "U1") (pin "J4_9") (pinfunction "0_J4_9") (pintype "bidirectional"))
    )
    (net (code "65") (name "Net-(U1-1)") (class "Default")
      (node (ref "TBD2") (pin "5") (pinfunction "5_5") (pintype "passive"))
      (node (ref "U1") (pin "J4_10") (pinfunction "1_J4_10") (pintype "bidirectional"))
    )
    (net (code "66") (name "Net-(U1-2)") (class "Default")
      (node (ref "TBD2") (pin "6") (pinfunction "6_6") (pintype "passive"))
      (node (ref "U1") (pin "J4_11") (pinfunction "2_J4_11") (pintype "bidirectional"))
    )
    (net (code "67") (name "Net-(U1-3)") (class "Default")
      (node (ref "TBD1") (pin "8") (pinfunction "8_8") (pintype "passive"))
      (node (ref "U1") (pin "J4_12") (pinfunction "3_J4_12") (pintype "bidirectional"))
    )
    (net (code "68") (name "Net-(U1-4)") (class "Default")
      (node (ref "TBD1") (pin "7") (pinfunction "7_7") (pintype "passive"))
      (node (ref "U1") (pin "J4_13") (pinfunction "4_J4_13") (pintype "bidirectional"))
    )
    (net (code "69") (name "Net-(U1-5)") (class "Default")
      (node (ref "TBD1") (pin "6") (pinfunction "6_6") (pintype "passive"))
      (node (ref "U1") (pin "J4_14") (pinfunction "5_J4_14") (pintype "bidirectional"))
    )
    (net (code "70") (name "Net-(U1-6)") (class "Default")
      (node (ref "TBD1") (pin "3") (pinfunction "3_3") (pintype "passive"))
      (node (ref "U1") (pin "J5_1") (pinfunction "6_J5_1") (pintype "bidirectional"))
    )
    (net (code "71") (name "Net-(U1-7)") (class "Default")
      (node (ref "TBD1") (pin "4") (pinfunction "4_4") (pintype "passive"))
      (node (ref "U1") (pin "J5_2") (pinfunction "7_J5_2") (pintype "bidirectional"))
    )
    (net (code "72") (name "Net-(U1-8_MOSI)") (class "Default")
      (node (ref "TBD1") (pin "5") (pinfunction "5_5") (pintype "passive"))
      (node (ref "U1") (pin "J5_3") (pinfunction "8_MOSI_J5_3") (pintype "bidirectional"))
    )
    (net (code "73") (name "Net-(U1-9_SCK)") (class "Default")
      (node (ref "TBD2") (pin "1") (pinfunction "1_1") (pintype "passive"))
      (node (ref "U1") (pin "J5_4") (pinfunction "9_SCK_J5_4") (pintype "bidirectional"))
    )
    (net (code "74") (name "Net-(U1-10_MISO)") (class "Default")
      (node (ref "TBD2") (pin "2") (pinfunction "2_2") (pintype "passive"))
      (node (ref "U1") (pin "J5_5") (pinfunction "10_MISO_J5_5") (pintype "bidirectional"))
    )
    (net (code "75") (name "Net-(U1-13_RX)") (class "Default")
      (node (ref "R2") (pin "2") (pinfunction "2_2") (pintype "passive"))
      (node (ref "U1") (pin "J5_8") (pinfunction "13_RX_J5_8") (pintype "input"))
    )
    (net (code "76") (name "Net-(U1-14_TX)") (class "Default")
      (node (ref "R1") (pin "2") (pinfunction "2_2") (pintype "passive"))
      (node (ref "U1") (pin "J5_9") (pinfunction "14_TX_J5_9") (pintype "output"))
    )
    (net (code "77") (name "Net-(U1-A1)") (class "Default")
      (node (ref "C12") (pin "1") (pinfunction "1_1") (pintype "passive"))
      (node (ref "R19") (pin "2") (pinfunction "2_2") (pintype "passive"))
      (node (ref "R7") (pin "2") (pinfunction "2_2") (pintype "passive"))
      (node (ref "U1") (pin "J4_3") (pinfunction "A1_J4_3") (pintype "bidirectional"))
    )
    (net (code "78") (name "Net-(U1-DAC0{slash}A0)") (class "Default")
      (node (ref "R11") (pin "2") (pinfunction "2_2") (pintype "passive"))
      (node (ref "U1") (pin "J4_2") (pinfunction "DAC0/A0_J4_2") (pintype "bidirectional"))
    )
    (net (code "79") (name "Net-(U2-AN)") (class "Default")
      (node (ref "AN") (pin "1") (pinfunction "1_1") (pintype "passive"))
      (node (ref "U2") (pin "R_AN") (pinfunction "AN_R_AN") (pintype "bidirectional"))
    )
    (net (code "80") (name "Net-(U2-MISO)") (class "Default")
      (node (ref "R10") (pin "2") (pinfunction "2_2") (pintype "passive"))
      (node (ref "U2") (pin "R_MISO") (pinfunction "MISO_R_MISO") (pintype "bidirectional"))
    )
    (net (code "81") (name "Net-(U3-A)") (class "Default")
      (node (ref "U2") (pin "A") (pinfunction "A_A") (pintype "bidirectional"))
      (node (ref "U3") (pin "1") (pinfunction "A_1") (pintype "input"))
    )
    (net (code "82") (name "Net-(U3-B)") (class "Default")
      (node (ref "U2") (pin "B") (pinfunction "B_B") (pintype "bidirectional"))
      (node (ref "U3") (pin "2") (pinfunction "B_2") (pintype "input"))
    )
    (net (code "83") (name "Net-(X8-KL)") (class "Default")
      (node (ref "R25") (pin "2") (pinfunction "2_2") (pintype "passive"))
      (node (ref "X8") (pin "1") (pinfunction "KL_1") (pintype "passive"))
    )
    (net (code "84") (name "Net-(X8-KL1)") (class "Default")
      (node (ref "R24") (pin "2") (pinfunction "2_2") (pintype "passive"))
      (node (ref "X8") (pin "2") (pinfunction "KL1_2") (pintype "passive"))
    )
    (net (code "85") (name "VDD") (class "Default")
      (node (ref "DS1") (pin "2") (pinfunction "A1_2") (pintype "passive"))
      (node (ref "DS1") (pin "5") (pinfunction "A4_5") (pintype "passive"))
      (node (ref "DS2") (pin "2") (pinfunction "A1_2") (pintype "passive"))
      (node (ref "DS2") (pin "5") (pinfunction "A4_5") (pintype "passive"))
      (node (ref "DS3") (pin "2") (pinfunction "A1_2") (pintype "passive"))
      (node (ref "DS3") (pin "5") (pinfunction "A4_5") (pintype "passive"))
      (node (ref "DS4") (pin "2") (pinfunction "A1_2") (pintype "passive"))
      (node (ref "DS4") (pin "5") (pinfunction "A4_5") (pintype "passive"))
      (node (ref "R17") (pin "2") (pinfunction "2_2") (pintype "passive"))
      (node (ref "R6") (pin "2") (pinfunction "2_2") (pintype "passive"))
      (node (ref "T1") (pin "2") (pinfunction "S_2") (pintype "passive"))
      (node (ref "U1") (pin "J5_12") (pinfunction "3V3_J5_12") (pintype "power_in"))
    )
    (net (code "86") (name "unconnected-(DS4-C-Pad6)") (class "Default")
      (node (ref "DS4") (pin "6") (pinfunction "C_6") (pintype "passive"))
    )
    (net (code "87") (name "unconnected-(K1-Pad1)") (class "Default")
      (node (ref "K1") (pin "1") (pinfunction "1_1") (pintype "passive"))
    )
    (net (code "88") (name "unconnected-(K1-Pad3)") (class "Default")
      (node (ref "K1") (pin "3") (pinfunction "3_3") (pintype "passive"))
    )
    (net (code "89") (name "unconnected-(K1-Pad4)") (class "Default")
      (node (ref "K1") (pin "4") (pinfunction "4_4") (pintype "passive"))
    )
    (net (code "90") (name "unconnected-(K1-Pad5)") (class "Default")
      (node (ref "K1") (pin "5") (pinfunction "5_5") (pintype "passive"))
    )
    (net (code "91") (name "unconnected-(K1-Pad7)") (class "Default")
      (node (ref "K1") (pin "7") (pinfunction "7_7") (pintype "passive"))
    )
    (net (code "92") (name "unconnected-(K1-Pad11)") (class "Default")
      (node (ref "K1") (pin "11") (pinfunction "11_11") (pintype "passive"))
    )
    (net (code "93") (name "unconnected-(K1-Pad12)") (class "Default")
      (node (ref "K1") (pin "12") (pinfunction "12_12") (pintype "passive"))
    )
    (net (code "94") (name "unconnected-(K1-Pad17)") (class "Default")
      (node (ref "K1") (pin "17") (pinfunction "17_17") (pintype "passive"))
    )
    (net (code "95") (name "unconnected-(K1-Pad19)") (class "Default")
      (node (ref "K1") (pin "19") (pinfunction "19_19") (pintype "passive"))
    )
    (net (code "96") (name "unconnected-(K1-Pad26)") (class "Default")
      (node (ref "K1") (pin "26") (pinfunction "26_26") (pintype "passive"))
    )
    (net (code "97") (name "unconnected-(K1-Pad27)") (class "Default")
      (node (ref "K1") (pin "27") (pinfunction "27_27") (pintype "passive"))
    )
    (net (code "98") (name "unconnected-(K1-Pad28)") (class "Default")
      (node (ref "K1") (pin "28") (pinfunction "28_28") (pintype "passive"))
    )
    (net (code "99") (name "unconnected-(K1-Pad35)") (class "Default")
      (node (ref "K1") (pin "35") (pinfunction "35_35") (pintype "passive"))
    )
    (net (code "100") (name "unconnected-(K1-Pad38)") (class "Default")
      (node (ref "K1") (pin "38") (pinfunction "38_38") (pintype "passive"))
    )
    (net (code "101") (name "unconnected-(K1-Pad40)") (class "Default")
      (node (ref "K1") (pin "40") (pinfunction "40_40") (pintype "passive"))
    )
    (net (code "102") (name "unconnected-(U1-11_SDA-PadJ5_6)") (class "Default")
      (node (ref "U1") (pin "J5_6") (pinfunction "11_SDA_J5_6") (pintype "bidirectional"))
    )
    (net (code "103") (name "unconnected-(U1-12_SCL-PadJ5_7)") (class "Default")
      (node (ref "U1") (pin "J5_7") (pinfunction "12_SCL_J5_7") (pintype "bidirectional"))
    )
    (net (code "104") (name "unconnected-(U1-RESET-PadJ5_10)") (class "Default")
      (node (ref "U1") (pin "J5_10") (pinfunction "RESET_J5_10") (pintype "bidirectional"))
    )
    (net (code "105") (name "unconnected-(U2-3V3-PadR_3.3V)") (class "Default")
      (node (ref "U2") (pin "R_3.3V") (pinfunction "3V3_R_3.3V") (pintype "bidirectional"))
    )
    (net (code "106") (name "unconnected-(U2-MOSI-PadR_MOSI)") (class "Default")
      (node (ref "U2") (pin "R_MOSI") (pinfunction "MOSI_R_MOSI") (pintype "bidirectional"))
    )
    (net (code "107") (name "unconnected-(U2-RX-PadR_RX)") (class "Default")
      (node (ref "U2") (pin "R_RX") (pinfunction "RX_R_RX") (pintype "bidirectional"))
    )
    (net (code "108") (name "unconnected-(U2-SCL-PadR_SCL)") (class "Default")
      (node (ref "U2") (pin "R_SCL") (pinfunction "SCL_R_SCL") (pintype "bidirectional"))
    )
    (net (code "109") (name "unconnected-(U2-SDA-PadR_SDA)") (class "Default")
      (node (ref "U2") (pin "R_SDA") (pinfunction "SDA_R_SDA") (pintype "bidirectional"))
    )
    (net (code "110") (name "unconnected-(U2-TX-PadR_TX)") (class "Default")
      (node (ref "U2") (pin "R_TX") (pinfunction "TX_R_TX") (pintype "bidirectional"))
    )
    (net (code "111") (name "unconnected-(X1-Pad4)") (class "Default")
      (node (ref "X1") (pin "4") (pinfunction "4_4") (pintype "passive"))
    )
    (net (code "112") (name "unconnected-(X2-Pad4)") (class "Default")
      (node (ref "X2") (pin "4") (pinfunction "4_4") (pintype "passive"))
    )
    (net (code "113") (name "unconnected-(X2-Pad6)") (class "Default")
      (node (ref "X2") (pin "6") (pinfunction "6_6") (pintype "passive"))
    )
  )
)
